# RS485.net
KiCad netlist of a schematic drawn in Altium Designer
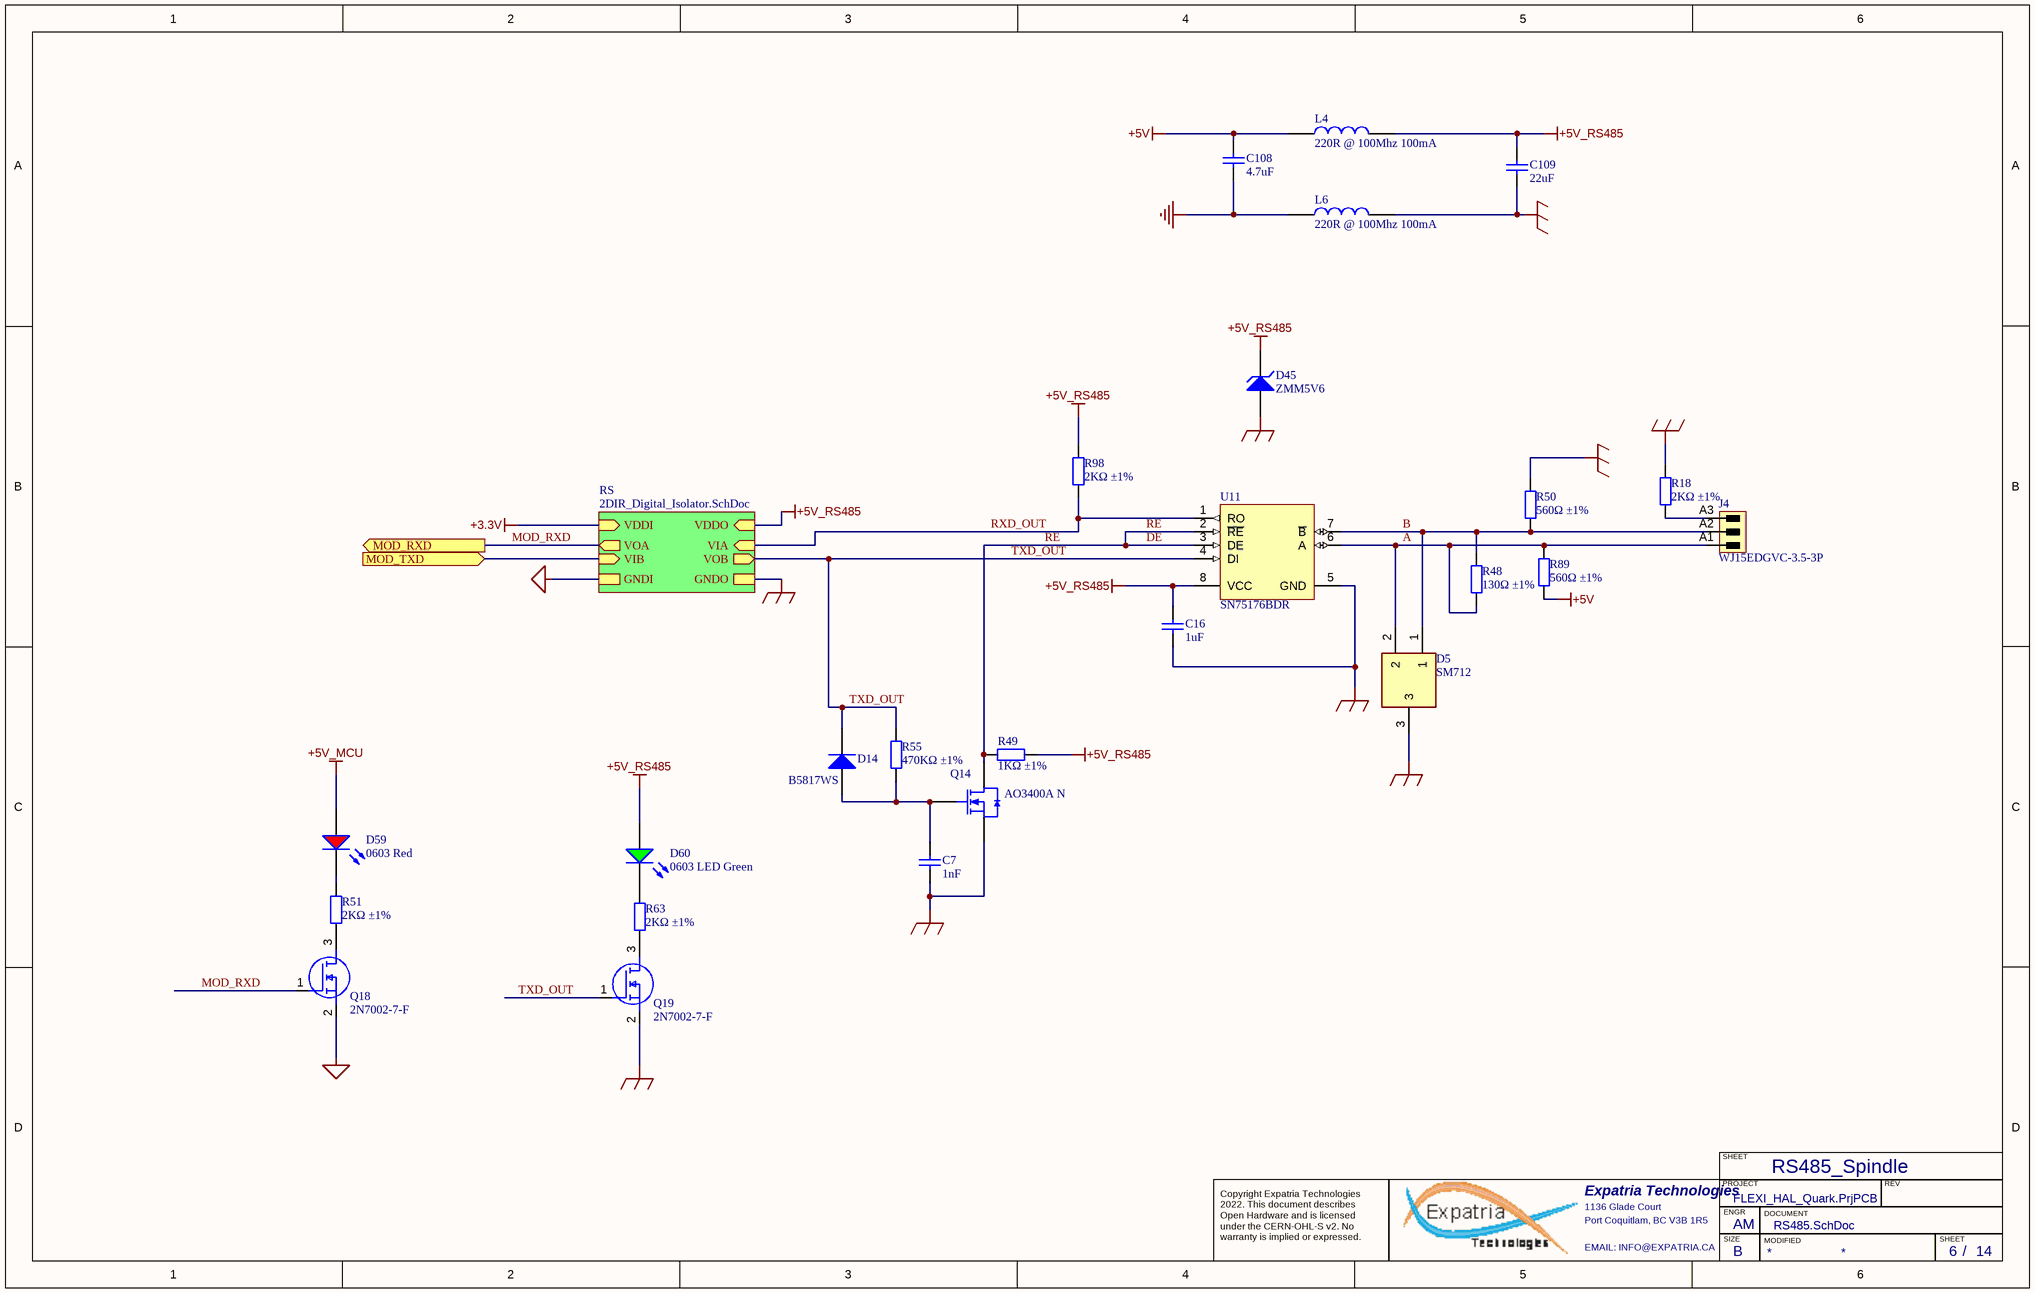
[diagram p0: RS485.SchDoc]

(export (version "E")
  (design (tool "Eeschema 10.0.6"))
  (components
    (comp (ref "C7")
      (value "1nF")
      (footprint "0603_C")
      (description "Chip capacitors")
      (fields
        (field (name "MANUFACTURER") "Samsung Electro-Mechanics")
        (field (name "PARTNUMBER") "CL10B102KB8NNNC")
      )
      (libsource (lib "Cap") (part "0603 1nF (102) 10% 50V"))
    )
    (comp (ref "C16")
      (value "1uF")
      (footprint "0603_C")
      (description "Chip capacitors")
      (fields
        (field (name "MANUFACTURER") "Samsung Electro-Mechanics")
        (field (name "PARTNUMBER") "CL10A105KB8NNNC")
      )
      (libsource (lib "Cap") (part "0603 1uF (105) 10% 50V"))
    )
    (comp (ref "C108")
      (value "4.7uF")
      (footprint "0805_C")
      (description "Chip capacitors")
      (fields
        (field (name "MANUFACTURER") "Samsung Electro-Mechanics")
        (field (name "PARTNUMBER") "CL21A475KAQNNNE")
      )
      (libsource (lib "Cap") (part "0805 4.7uF (475) 10% 25V"))
    )
    (comp (ref "C109")
      (value "22uF")
      (footprint "0805_C")
      (description "Chip capacitors")
      (fields
        (field (name "MANUFACTURER") "Samsung Electro-Mechanics")
        (field (name "PARTNUMBER") "CL21A226MAQNNNE")
      )
      (libsource (lib "Cap") (part "0805 22uF (226) 20% 25V"))
    )
    (comp (ref "D5")
      (value "SM712")
      (footprint "SamacSys:SOT95P230X117-3N")
      (description "Bidirectional 12V (Max), 7V (Max) 7.5V / 13.3V 10V / 20V 12A(8/20us) SOT-23-3 TVS RoHS")
      (libsource (lib "*") (part "CDSOT23-SM712"))
    )
    (comp (ref "D14")
      (value "B5817WS")
      (footprint "SOD-323")
      (description "20V 750mV@3A 1A SOD-323 Schottky Barrier Diodes (SBD) ROHS")
      (libsource (lib "Diode") (part "SOD-123 B5819W  SL"))
    )
    (comp (ref "D45")
      (value "ZMM5V6")
      (footprint "LL-34")
      (description "500mW - 0.1uA @ 1V 5.6V LL-34 Zener Diodes ROHS")
      (libsource (lib "Zener") (part "LL-34 ZMM5V6"))
    )
    (comp (ref "D59")
      (value "0603 Red")
      (footprint "0603_LED_S1")
      (fields
        (field (name "MANUFACTURER") "Everlight Elec")
        (field (name "MANUFACTURER PART NUMBER") "19-213SURC/S530-A3/TR8")
      )
      (libsource (lib "Sienci_Labs") (part "19-213SURC/S530-A3/TR8"))
    )
    (comp (ref "D60")
      (value "0603 LED Green")
      (footprint "0603_LED_S1")
      (fields
        (field (name "MANUFACTURER PART NUMBER") "19-217/GHC-YR1S2/3T")
        (field (name "MANUFACTURER") "Everlight Elec")
      )
      (libsource (lib "Sienci_Labs") (part "19-217/GHC-YR1S2/3T"))
    )
    (comp (ref "J4")
      (value "WJ15EDGVC-3.5-3P")
      (footprint "691321100003 - 3.5mm  3p")
      (fields (field (name "MANUFACTURER") "Ningbo Kangnex Elec"))
      (libsource (lib "Universal_CNC_Breakout") (part "3.5mm Terminal Header 3p"))
    )
    (comp (ref "L4")
      (value "220R @ 100Mhz 100mA")
      (footprint "0402_L")
      (description "Ferrite Bead")
      (libsource (lib "FBEAD") (part "0402 220R@100Mhz 0.1A"))
    )
    (comp (ref "L6")
      (value "220R @ 100Mhz 100mA")
      (footprint "0402_L")
      (description "Ferrite Bead")
      (libsource (lib "FBEAD") (part "0402 220R@100Mhz 0.1A"))
    )
    (comp (ref "Q14")
      (value "AO3400A N")
      (footprint "SOT-23-3L")
      (description "MOS(场效应管)")
      (libsource (lib "MOS") (part "AO3400A N道沟 X0YV1T SOT-23"))
    )
    (comp (ref "Q18")
      (value "2N7002-7-F")
      (footprint "SOT-23(SOT-23-3)")
      (description "60V 115mA 7.5Ω@5V,50mA 370mW N Channel SOT-23 MOSFETs ROHS")
      (fields (field (name "MANUFACTURER") "Diodes Inc.") (field (name "MOUSER PART NUMBER") "621-2N7002-F"))
      (libsource (lib "Sienci_Labs") (part "2N7002-7-F"))
    )
    (comp (ref "Q19")
      (value "2N7002-7-F")
      (footprint "SOT-23(SOT-23-3)")
      (description "60V 115mA 7.5Ω@5V,50mA 370mW N Channel SOT-23 MOSFETs ROHS")
      (fields (field (name "MANUFACTURER") "Diodes Inc.") (field (name "MOUSER PART NUMBER") "621-2N7002-F"))
      (libsource (lib "Sienci_Labs") (part "2N7002-7-F"))
    )
    (comp (ref "R18")
      (value "2KΩ ±1%")
      (footprint "0603_R")
      (description "Chip resistor")
      (fields (field (name "MANUFACTURER") "Uniroyal Elec") (field (name "PARTNUMBER") "0603WAF2001T5E"))
      (libsource (lib "") (part "0603 2K (2001) 1%_1"))
    )
    (comp (ref "R48")
      (value "130Ω ±1%")
      (footprint "0603_R")
      (description "Chip resistor")
      (fields (field (name "MANUFACTURER") "Uniroyal Elec") (field (name "PARTNUMBER") "0603WAF1300T5E"))
      (libsource (lib "RES") (part "0603 130R (1300) 1%"))
    )
    (comp (ref "R49")
      (value "1KΩ ±1%")
      (footprint "0603_R")
      (description "Chip resistor")
      (fields (field (name "MANUFACTURER") "Uniroyal Elec") (field (name "PARTNUMBER") "0603WAF1001T5E"))
      (libsource (lib "RES") (part "0603 1K (1001) 1%"))
    )
    (comp (ref "R50")
      (value "560Ω ±1%")
      (footprint "0603_R")
      (description "Chip resistor")
      (fields (field (name "MANUFACTURER") "Uniroyal Elec") (field (name "PARTNUMBER") "0603WAF5600T5E"))
      (libsource (lib "RES") (part "0603 560R (5600) 1%"))
    )
    (comp (ref "R51")
      (value "2KΩ ±1%")
      (footprint "0402_R")
      (description "Chip resistor")
      (fields
        (field (name "MANUFACTURER") "Uniroyal Elec")
        (field (name "MANUFACTURER PART NUMBER") "0402WGF2001TCE")
      )
      (libsource (lib "RES") (part "0402 2K (2001) 1%"))
    )
    (comp (ref "R55")
      (value "470KΩ ±1%")
      (footprint "0603_R")
      (description "Chip resistor")
      (fields (field (name "MANUFACTURER") "Uniroyal Elec") (field (name "PARTNUMBER") "0603WAF4703T5E"))
      (libsource (lib "RES") (part "0603 470K (4703) 1%"))
    )
    (comp (ref "R63")
      (value "2KΩ ±1%")
      (footprint "0402_R")
      (description "Chip resistor")
      (fields
        (field (name "MANUFACTURER") "Uniroyal Elec")
        (field (name "MANUFACTURER PART NUMBER") "0402WGF2001TCE")
      )
      (libsource (lib "RES") (part "0402 2K (2001) 1%"))
    )
    (comp (ref "R89")
      (value "560Ω ±1%")
      (footprint "0603_R")
      (description "Chip resistor")
      (fields (field (name "MANUFACTURER") "Uniroyal Elec") (field (name "PARTNUMBER") "0603WAF5600T5E"))
      (libsource (lib "RES") (part "0603 560R (5600) 1%"))
    )
    (comp (ref "R98")
      (value "2KΩ ±1%")
      (footprint "0603_R")
      (description "Chip resistor")
      (fields (field (name "MANUFACTURER") "Uniroyal Elec") (field (name "PARTNUMBER") "0603WAF2001T5E"))
      (libsource (lib "RES") (part "0603 2K (2001) 1%"))
    )
    (comp (ref "U11")
      (value "SN75176BDR")
      (footprint "SOIC-8_150mil")
      (description "RS-485/RS-422")
      (libsource (lib "IC") (part "SN75176BDR_[C7063]"))
    )
  )
  (nets
    (net (code "2") (name "+5V") (class "Default")
      (node (ref "C108") (pin "2") (pinfunction "2_2") (pintype "passive"))
      (node (ref "L4") (pin "1") (pinfunction "1_1") (pintype "passive"))
      (node (ref "R89") (pin "2") (pinfunction "2_2") (pintype "passive"))
    )
    (net (code "3") (name "+5V_MCU") (class "Default")
      (node (ref "D59") (pin "A") (pinfunction "A_A") (pintype "passive"))
    )
    (net (code "4") (name "+5V_RS485") (class "Default")
      (node (ref "C109") (pin "2") (pinfunction "2_2") (pintype "passive"))
      (node (ref "C16") (pin "2") (pinfunction "2_2") (pintype "passive"))
      (node (ref "D45") (pin "2") (pinfunction "K_2") (pintype "passive"))
      (node (ref "D60") (pin "A") (pinfunction "A_A") (pintype "passive"))
      (node (ref "L4") (pin "2") (pinfunction "2_2") (pintype "passive"))
      (node (ref "R49") (pin "1") (pinfunction "1_1") (pintype "passive"))
      (node (ref "R98") (pin "2") (pinfunction "2_2") (pintype "passive"))
      (node (ref "U11") (pin "8") (pinfunction "VCC_8") (pintype "power_in"))
    )
    (net (code "5") (name "/A") (class "Default")
      (node (ref "D5") (pin "2") (pinfunction "2_2") (pintype "passive"))
      (node (ref "J4") (pin "A1") (pinfunction "A1_A1") (pintype "passive"))
      (node (ref "R48") (pin "1") (pinfunction "1_1") (pintype "passive"))
      (node (ref "R89") (pin "1") (pinfunction "1_1") (pintype "passive"))
      (node (ref "U11") (pin "6") (pinfunction "A_6") (pintype "bidirectional"))
    )
    (net (code "6") (name "/B") (class "Default")
      (node (ref "D5") (pin "1") (pinfunction "1_1") (pintype "passive"))
      (node (ref "J4") (pin "A2") (pinfunction "A2_A2") (pintype "passive"))
      (node (ref "R48") (pin "2") (pinfunction "2_2") (pintype "passive"))
      (node (ref "R50") (pin "2") (pinfunction "2_2") (pintype "passive"))
      (node (ref "U11") (pin "7") (pinfunction "~{B}_7") (pintype "bidirectional"))
    )
    (net (code "7") (name "/DE") (class "Default")
      (node (ref "Q14") (pin "3") (pinfunction "D_3") (pintype "passive"))
      (node (ref "R49") (pin "2") (pinfunction "2_2") (pintype "passive"))
      (node (ref "U11") (pin "2") (pinfunction "~{RE}_2") (pintype "input"))
      (node (ref "U11") (pin "3") (pinfunction "DE_3") (pintype "input"))
    )
    (net (code "8") (name "/MOD_RXD") (class "Default")
      (node (ref "Q18") (pin "1") (pinfunction "G_1") (pintype "passive"))
    )
    (net (code "10") (name "/RXD_OUT") (class "Default")
      (node (ref "R98") (pin "1") (pinfunction "1_1") (pintype "passive"))
      (node (ref "U11") (pin "1") (pinfunction "RO_1") (pintype "output"))
    )
    (net (code "11") (name "/TXD_OUT") (class "Default")
      (node (ref "D14") (pin "2") (pinfunction "K_2") (pintype "passive"))
      (node (ref "Q19") (pin "1") (pinfunction "G_1") (pintype "passive"))
      (node (ref "R55") (pin "1") (pinfunction "1_1") (pintype "passive"))
      (node (ref "U11") (pin "4") (pinfunction "DI_4") (pintype "input"))
    )
    (net (code "12") (name "GND") (class "Default")
      (node (ref "C108") (pin "1") (pinfunction "1_1") (pintype "passive"))
      (node (ref "L6") (pin "1") (pinfunction "1_1") (pintype "passive"))
    )
    (net (code "13") (name "MCU_GND") (class "Default")
      (node (ref "Q18") (pin "2") (pinfunction "S_2") (pintype "passive"))
    )
    (net (code "14") (name "MOD_GND") (class "Default")
      (node (ref "C109") (pin "1") (pinfunction "1_1") (pintype "passive"))
      (node (ref "C16") (pin "1") (pinfunction "1_1") (pintype "passive"))
      (node (ref "C7") (pin "2") (pinfunction "2_2") (pintype "passive"))
      (node (ref "D45") (pin "1") (pinfunction "A_1") (pintype "passive"))
      (node (ref "D5") (pin "3") (pinfunction "3_3") (pintype "passive"))
      (node (ref "L6") (pin "2") (pinfunction "2_2") (pintype "passive"))
      (node (ref "Q14") (pin "2") (pinfunction "S_2") (pintype "passive"))
      (node (ref "Q19") (pin "2") (pinfunction "S_2") (pintype "passive"))
      (node (ref "R18") (pin "1") (pinfunction "1_1") (pintype "passive"))
      (node (ref "R50") (pin "1") (pinfunction "1_1") (pintype "passive"))
      (node (ref "U11") (pin "5") (pinfunction "GND_5") (pintype "power_in"))
    )
    (net (code "15") (name "Net-(D14-A)") (class "Default")
      (node (ref "C7") (pin "1") (pinfunction "1_1") (pintype "passive"))
      (node (ref "D14") (pin "1") (pinfunction "A_1") (pintype "passive"))
      (node (ref "Q14") (pin "1") (pinfunction "G_1") (pintype "passive"))
      (node (ref "R55") (pin "2") (pinfunction "2_2") (pintype "passive"))
    )
    (net (code "16") (name "Net-(D59-PadK)") (class "Default")
      (node (ref "D59") (pin "K") (pinfunction "K_K") (pintype "passive"))
      (node (ref "R51") (pin "2") (pinfunction "2_2") (pintype "passive"))
    )
    (net (code "17") (name "Net-(D60-PadK)") (class "Default")
      (node (ref "D60") (pin "K") (pinfunction "K_K") (pintype "passive"))
      (node (ref "R63") (pin "2") (pinfunction "2_2") (pintype "passive"))
    )
    (net (code "18") (name "Net-(J4-PadA3)") (class "Default")
      (node (ref "J4") (pin "A3") (pinfunction "A3_A3") (pintype "passive"))
      (node (ref "R18") (pin "2") (pinfunction "2_2") (pintype "passive"))
    )
    (net (code "19") (name "Net-(Q18-D)") (class "Default")
      (node (ref "Q18") (pin "3") (pinfunction "D_3") (pintype "passive"))
      (node (ref "R51") (pin "1") (pinfunction "1_1") (pintype "passive"))
    )
    (net (code "20") (name "Net-(Q19-D)") (class "Default")
      (node (ref "Q19") (pin "3") (pinfunction "D_3") (pintype "passive"))
      (node (ref "R63") (pin "1") (pinfunction "1_1") (pintype "passive"))
    )
  )
)
